# counter.net
KiCad netlist of a schematic drawn in EAGLE
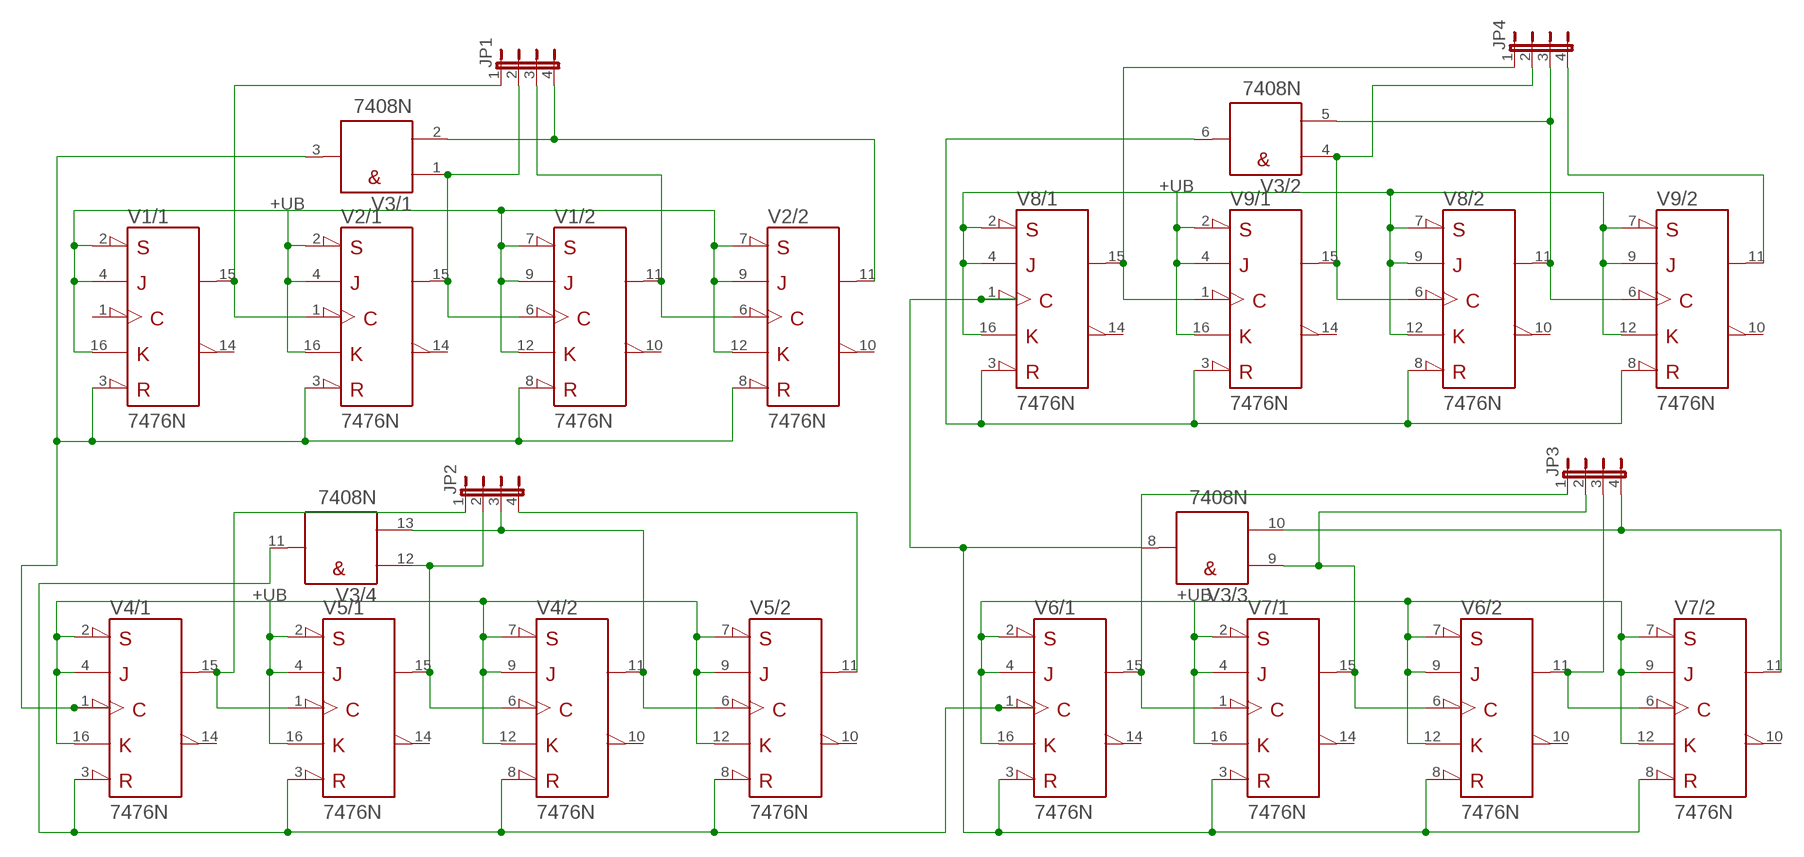
[diagram p0: schematic, sheet 1]

(export (version "E")
  (design (tool "Eeschema 10.0.6"))
  (components
    (comp (ref "JP1")
      (value "JP4E")
      (footprint "eagle-import:JP4")
      (libsource (lib "eagle-import") (part "JP4E"))
    )
    (comp (ref "JP2")
      (value "JP4E")
      (footprint "eagle-import:JP4")
      (libsource (lib "eagle-import") (part "JP4E"))
    )
    (comp (ref "JP3")
      (value "JP4E")
      (footprint "eagle-import:JP4")
      (libsource (lib "eagle-import") (part "JP4E"))
    )
    (comp (ref "JP4")
      (value "JP4E")
      (footprint "eagle-import:JP4")
      (libsource (lib "eagle-import") (part "JP4E"))
    )
    (comp (ref "V1")
      (value "7476N")
      (footprint "eagle-import:DIL16")
      (libsource (lib "eagle-import") (part "7476N"))
    )
    (comp (ref "V2")
      (value "7476N")
      (footprint "eagle-import:DIL16")
      (libsource (lib "eagle-import") (part "7476N"))
    )
    (comp (ref "V3")
      (value "7408N")
      (footprint "eagle-import:DIL14")
      (libsource (lib "eagle-import") (part "7408N"))
    )
    (comp (ref "V4")
      (value "7476N")
      (footprint "eagle-import:DIL16")
      (libsource (lib "eagle-import") (part "7476N"))
    )
    (comp (ref "V5")
      (value "7476N")
      (footprint "eagle-import:DIL16")
      (libsource (lib "eagle-import") (part "7476N"))
    )
    (comp (ref "V6")
      (value "7476N")
      (footprint "eagle-import:DIL16")
      (libsource (lib "eagle-import") (part "7476N"))
    )
    (comp (ref "V7")
      (value "7476N")
      (footprint "eagle-import:DIL16")
      (libsource (lib "eagle-import") (part "7476N"))
    )
    (comp (ref "V8")
      (value "7476N")
      (footprint "eagle-import:DIL16")
      (libsource (lib "eagle-import") (part "7476N"))
    )
    (comp (ref "V9")
      (value "7476N")
      (footprint "eagle-import:DIL16")
      (libsource (lib "eagle-import") (part "7476N"))
    )
  )
  (nets
    (net (code "1") (name "/+UB") (class "Default")
      (node (ref "V1") (pin "12") (pinfunction "K_12") (pintype "input"))
      (node (ref "V1") (pin "16") (pinfunction "K_16") (pintype "input"))
      (node (ref "V1") (pin "2") (pinfunction "~{PRE}_2") (pintype "input"))
      (node (ref "V1") (pin "4") (pinfunction "J_4") (pintype "input"))
      (node (ref "V1") (pin "7") (pinfunction "~{PRE}_7") (pintype "input"))
      (node (ref "V1") (pin "9") (pinfunction "J_9") (pintype "input"))
      (node (ref "V2") (pin "12") (pinfunction "K_12") (pintype "input"))
      (node (ref "V2") (pin "16") (pinfunction "K_16") (pintype "input"))
      (node (ref "V2") (pin "2") (pinfunction "~{PRE}_2") (pintype "input"))
      (node (ref "V2") (pin "4") (pinfunction "J_4") (pintype "input"))
      (node (ref "V2") (pin "7") (pinfunction "~{PRE}_7") (pintype "input"))
      (node (ref "V2") (pin "9") (pinfunction "J_9") (pintype "input"))
      (node (ref "V4") (pin "12") (pinfunction "K_12") (pintype "input"))
      (node (ref "V4") (pin "16") (pinfunction "K_16") (pintype "input"))
      (node (ref "V4") (pin "2") (pinfunction "~{PRE}_2") (pintype "input"))
      (node (ref "V4") (pin "4") (pinfunction "J_4") (pintype "input"))
      (node (ref "V4") (pin "7") (pinfunction "~{PRE}_7") (pintype "input"))
      (node (ref "V4") (pin "9") (pinfunction "J_9") (pintype "input"))
      (node (ref "V5") (pin "12") (pinfunction "K_12") (pintype "input"))
      (node (ref "V5") (pin "16") (pinfunction "K_16") (pintype "input"))
      (node (ref "V5") (pin "2") (pinfunction "~{PRE}_2") (pintype "input"))
      (node (ref "V5") (pin "4") (pinfunction "J_4") (pintype "input"))
      (node (ref "V5") (pin "7") (pinfunction "~{PRE}_7") (pintype "input"))
      (node (ref "V5") (pin "9") (pinfunction "J_9") (pintype "input"))
      (node (ref "V6") (pin "12") (pinfunction "K_12") (pintype "input"))
      (node (ref "V6") (pin "16") (pinfunction "K_16") (pintype "input"))
      (node (ref "V6") (pin "2") (pinfunction "~{PRE}_2") (pintype "input"))
      (node (ref "V6") (pin "4") (pinfunction "J_4") (pintype "input"))
      (node (ref "V6") (pin "7") (pinfunction "~{PRE}_7") (pintype "input"))
      (node (ref "V6") (pin "9") (pinfunction "J_9") (pintype "input"))
      (node (ref "V7") (pin "12") (pinfunction "K_12") (pintype "input"))
      (node (ref "V7") (pin "16") (pinfunction "K_16") (pintype "input"))
      (node (ref "V7") (pin "2") (pinfunction "~{PRE}_2") (pintype "input"))
      (node (ref "V7") (pin "4") (pinfunction "J_4") (pintype "input"))
      (node (ref "V7") (pin "7") (pinfunction "~{PRE}_7") (pintype "input"))
      (node (ref "V7") (pin "9") (pinfunction "J_9") (pintype "input"))
      (node (ref "V8") (pin "12") (pinfunction "K_12") (pintype "input"))
      (node (ref "V8") (pin "16") (pinfunction "K_16") (pintype "input"))
      (node (ref "V8") (pin "2") (pinfunction "~{PRE}_2") (pintype "input"))
      (node (ref "V8") (pin "4") (pinfunction "J_4") (pintype "input"))
      (node (ref "V8") (pin "7") (pinfunction "~{PRE}_7") (pintype "input"))
      (node (ref "V8") (pin "9") (pinfunction "J_9") (pintype "input"))
      (node (ref "V9") (pin "12") (pinfunction "K_12") (pintype "input"))
      (node (ref "V9") (pin "16") (pinfunction "K_16") (pintype "input"))
      (node (ref "V9") (pin "2") (pinfunction "~{PRE}_2") (pintype "input"))
      (node (ref "V9") (pin "4") (pinfunction "J_4") (pintype "input"))
      (node (ref "V9") (pin "7") (pinfunction "~{PRE}_7") (pintype "input"))
      (node (ref "V9") (pin "9") (pinfunction "J_9") (pintype "input"))
    )
    (net (code "2") (name "Net-(V1C-Q)") (class "Default")
      (node (ref "JP1") (pin "1") (pinfunction "1_1") (pintype "passive"))
      (node (ref "V1") (pin "15") (pinfunction "Q_15") (pintype "output"))
      (node (ref "V2") (pin "1") (pinfunction "CLK_1") (pintype "input"))
    )
    (net (code "3") (name "Net-(V1C-~{CLR})") (class "Default")
      (node (ref "V1") (pin "3") (pinfunction "~{CLR}_3") (pintype "input"))
      (node (ref "V1") (pin "8") (pinfunction "~{CLR}_8") (pintype "input"))
      (node (ref "V2") (pin "3") (pinfunction "~{CLR}_3") (pintype "input"))
      (node (ref "V2") (pin "8") (pinfunction "~{CLR}_8") (pintype "input"))
      (node (ref "V3") (pin "3") (pinfunction "Y_3") (pintype "output"))
      (node (ref "V4") (pin "1") (pinfunction "CLK_1") (pintype "input"))
    )
    (net (code "4") (name "Net-(V1D-CLK)") (class "Default")
      (node (ref "JP1") (pin "2") (pinfunction "2_2") (pintype "passive"))
      (node (ref "V1") (pin "6") (pinfunction "CLK_6") (pintype "input"))
      (node (ref "V2") (pin "15") (pinfunction "Q_15") (pintype "output"))
      (node (ref "V3") (pin "1") (pinfunction "A_1") (pintype "input"))
    )
    (net (code "5") (name "Net-(V1D-Q)") (class "Default")
      (node (ref "JP1") (pin "3") (pinfunction "3_3") (pintype "passive"))
      (node (ref "V1") (pin "11") (pinfunction "Q_11") (pintype "output"))
      (node (ref "V2") (pin "6") (pinfunction "CLK_6") (pintype "input"))
    )
    (net (code "6") (name "Net-(V2D-Q)") (class "Default")
      (node (ref "JP1") (pin "4") (pinfunction "4_4") (pintype "passive"))
      (node (ref "V2") (pin "11") (pinfunction "Q_11") (pintype "output"))
      (node (ref "V3") (pin "2") (pinfunction "B_2") (pintype "input"))
    )
    (net (code "7") (name "Net-(V3D-A)") (class "Default")
      (node (ref "JP4") (pin "2") (pinfunction "2_2") (pintype "passive"))
      (node (ref "V3") (pin "4") (pinfunction "A_4") (pintype "input"))
      (node (ref "V8") (pin "6") (pinfunction "CLK_6") (pintype "input"))
      (node (ref "V9") (pin "15") (pinfunction "Q_15") (pintype "output"))
    )
    (net (code "8") (name "Net-(V3D-B)") (class "Default")
      (node (ref "JP4") (pin "3") (pinfunction "3_3") (pintype "passive"))
      (node (ref "V3") (pin "5") (pinfunction "B_5") (pintype "input"))
      (node (ref "V8") (pin "11") (pinfunction "Q_11") (pintype "output"))
      (node (ref "V9") (pin "6") (pinfunction "CLK_6") (pintype "input"))
    )
    (net (code "9") (name "Net-(V3D-Y)") (class "Default")
      (node (ref "V3") (pin "6") (pinfunction "Y_6") (pintype "output"))
      (node (ref "V8") (pin "3") (pinfunction "~{CLR}_3") (pintype "input"))
      (node (ref "V8") (pin "8") (pinfunction "~{CLR}_8") (pintype "input"))
      (node (ref "V9") (pin "3") (pinfunction "~{CLR}_3") (pintype "input"))
      (node (ref "V9") (pin "8") (pinfunction "~{CLR}_8") (pintype "input"))
    )
    (net (code "10") (name "Net-(V3E-A)") (class "Default")
      (node (ref "JP3") (pin "2") (pinfunction "2_2") (pintype "passive"))
      (node (ref "V3") (pin "9") (pinfunction "A_9") (pintype "input"))
      (node (ref "V6") (pin "6") (pinfunction "CLK_6") (pintype "input"))
      (node (ref "V7") (pin "15") (pinfunction "Q_15") (pintype "output"))
    )
    (net (code "11") (name "Net-(V3E-B)") (class "Default")
      (node (ref "JP3") (pin "4") (pinfunction "4_4") (pintype "passive"))
      (node (ref "V3") (pin "10") (pinfunction "B_10") (pintype "input"))
      (node (ref "V7") (pin "11") (pinfunction "Q_11") (pintype "output"))
    )
    (net (code "12") (name "Net-(V3E-Y)") (class "Default")
      (node (ref "V3") (pin "8") (pinfunction "Y_8") (pintype "output"))
      (node (ref "V6") (pin "3") (pinfunction "~{CLR}_3") (pintype "input"))
      (node (ref "V6") (pin "8") (pinfunction "~{CLR}_8") (pintype "input"))
      (node (ref "V7") (pin "3") (pinfunction "~{CLR}_3") (pintype "input"))
      (node (ref "V7") (pin "8") (pinfunction "~{CLR}_8") (pintype "input"))
      (node (ref "V8") (pin "1") (pinfunction "CLK_1") (pintype "input"))
    )
    (net (code "13") (name "Net-(V3F-A)") (class "Default")
      (node (ref "JP2") (pin "2") (pinfunction "2_2") (pintype "passive"))
      (node (ref "V3") (pin "12") (pinfunction "A_12") (pintype "input"))
      (node (ref "V4") (pin "6") (pinfunction "CLK_6") (pintype "input"))
      (node (ref "V5") (pin "15") (pinfunction "Q_15") (pintype "output"))
    )
    (net (code "14") (name "Net-(V3F-B)") (class "Default")
      (node (ref "JP2") (pin "3") (pinfunction "3_3") (pintype "passive"))
      (node (ref "V3") (pin "13") (pinfunction "B_13") (pintype "input"))
      (node (ref "V4") (pin "11") (pinfunction "Q_11") (pintype "output"))
      (node (ref "V5") (pin "6") (pinfunction "CLK_6") (pintype "input"))
    )
    (net (code "15") (name "Net-(V3F-Y)") (class "Default")
      (node (ref "V3") (pin "11") (pinfunction "Y_11") (pintype "output"))
      (node (ref "V4") (pin "3") (pinfunction "~{CLR}_3") (pintype "input"))
      (node (ref "V4") (pin "8") (pinfunction "~{CLR}_8") (pintype "input"))
      (node (ref "V5") (pin "3") (pinfunction "~{CLR}_3") (pintype "input"))
      (node (ref "V5") (pin "8") (pinfunction "~{CLR}_8") (pintype "input"))
      (node (ref "V6") (pin "1") (pinfunction "CLK_1") (pintype "input"))
    )
    (net (code "16") (name "Net-(V4C-Q)") (class "Default")
      (node (ref "JP2") (pin "1") (pinfunction "1_1") (pintype "passive"))
      (node (ref "V4") (pin "15") (pinfunction "Q_15") (pintype "output"))
      (node (ref "V5") (pin "1") (pinfunction "CLK_1") (pintype "input"))
    )
    (net (code "17") (name "Net-(V5D-Q)") (class "Default")
      (node (ref "JP2") (pin "4") (pinfunction "4_4") (pintype "passive"))
      (node (ref "V5") (pin "11") (pinfunction "Q_11") (pintype "output"))
    )
    (net (code "18") (name "Net-(V6C-Q)") (class "Default")
      (node (ref "JP3") (pin "1") (pinfunction "1_1") (pintype "passive"))
      (node (ref "V6") (pin "15") (pinfunction "Q_15") (pintype "output"))
      (node (ref "V7") (pin "1") (pinfunction "CLK_1") (pintype "input"))
    )
    (net (code "19") (name "Net-(V6D-Q)") (class "Default")
      (node (ref "JP3") (pin "3") (pinfunction "3_3") (pintype "passive"))
      (node (ref "V6") (pin "11") (pinfunction "Q_11") (pintype "output"))
      (node (ref "V7") (pin "6") (pinfunction "CLK_6") (pintype "input"))
    )
    (net (code "20") (name "Net-(V8C-Q)") (class "Default")
      (node (ref "JP4") (pin "1") (pinfunction "1_1") (pintype "passive"))
      (node (ref "V8") (pin "15") (pinfunction "Q_15") (pintype "output"))
      (node (ref "V9") (pin "1") (pinfunction "CLK_1") (pintype "input"))
    )
    (net (code "21") (name "Net-(V9D-Q)") (class "Default")
      (node (ref "JP4") (pin "4") (pinfunction "4_4") (pintype "passive"))
      (node (ref "V9") (pin "11") (pinfunction "Q_11") (pintype "output"))
    )
    (net (code "22") (name "unconnected-(V1C-CLK-Pad1)") (class "Default")
      (node (ref "V1") (pin "1") (pinfunction "CLK_1") (pintype "input"))
    )
    (net (code "23") (name "unconnected-(V1C-~{Q}-Pad14)") (class "Default")
      (node (ref "V1") (pin "14") (pinfunction "~{Q}_14") (pintype "output"))
    )
    (net (code "24") (name "unconnected-(V1D-~{Q}-Pad10)") (class "Default")
      (node (ref "V1") (pin "10") (pinfunction "~{Q}_10") (pintype "output"))
    )
    (net (code "25") (name "unconnected-(V2C-~{Q}-Pad14)") (class "Default")
      (node (ref "V2") (pin "14") (pinfunction "~{Q}_14") (pintype "output"))
    )
    (net (code "26") (name "unconnected-(V2D-~{Q}-Pad10)") (class "Default")
      (node (ref "V2") (pin "10") (pinfunction "~{Q}_10") (pintype "output"))
    )
    (net (code "27") (name "unconnected-(V4C-~{Q}-Pad14)") (class "Default")
      (node (ref "V4") (pin "14") (pinfunction "~{Q}_14") (pintype "output"))
    )
    (net (code "28") (name "unconnected-(V4D-~{Q}-Pad10)") (class "Default")
      (node (ref "V4") (pin "10") (pinfunction "~{Q}_10") (pintype "output"))
    )
    (net (code "29") (name "unconnected-(V5C-~{Q}-Pad14)") (class "Default")
      (node (ref "V5") (pin "14") (pinfunction "~{Q}_14") (pintype "output"))
    )
    (net (code "30") (name "unconnected-(V5D-~{Q}-Pad10)") (class "Default")
      (node (ref "V5") (pin "10") (pinfunction "~{Q}_10") (pintype "output"))
    )
    (net (code "31") (name "unconnected-(V6C-~{Q}-Pad14)") (class "Default")
      (node (ref "V6") (pin "14") (pinfunction "~{Q}_14") (pintype "output"))
    )
    (net (code "32") (name "unconnected-(V6D-~{Q}-Pad10)") (class "Default")
      (node (ref "V6") (pin "10") (pinfunction "~{Q}_10") (pintype "output"))
    )
    (net (code "33") (name "unconnected-(V7C-~{Q}-Pad14)") (class "Default")
      (node (ref "V7") (pin "14") (pinfunction "~{Q}_14") (pintype "output"))
    )
    (net (code "34") (name "unconnected-(V7D-~{Q}-Pad10)") (class "Default")
      (node (ref "V7") (pin "10") (pinfunction "~{Q}_10") (pintype "output"))
    )
    (net (code "35") (name "unconnected-(V8C-~{Q}-Pad14)") (class "Default")
      (node (ref "V8") (pin "14") (pinfunction "~{Q}_14") (pintype "output"))
    )
    (net (code "36") (name "unconnected-(V8D-~{Q}-Pad10)") (class "Default")
      (node (ref "V8") (pin "10") (pinfunction "~{Q}_10") (pintype "output"))
    )
    (net (code "37") (name "unconnected-(V9C-~{Q}-Pad14)") (class "Default")
      (node (ref "V9") (pin "14") (pinfunction "~{Q}_14") (pintype "output"))
    )
    (net (code "38") (name "unconnected-(V9D-~{Q}-Pad10)") (class "Default")
      (node (ref "V9") (pin "10") (pinfunction "~{Q}_10") (pintype "output"))
    )
  )
)
